# QCopterRC_MCU_Sch.net
KiCad netlist of a schematic drawn in Altium Designer
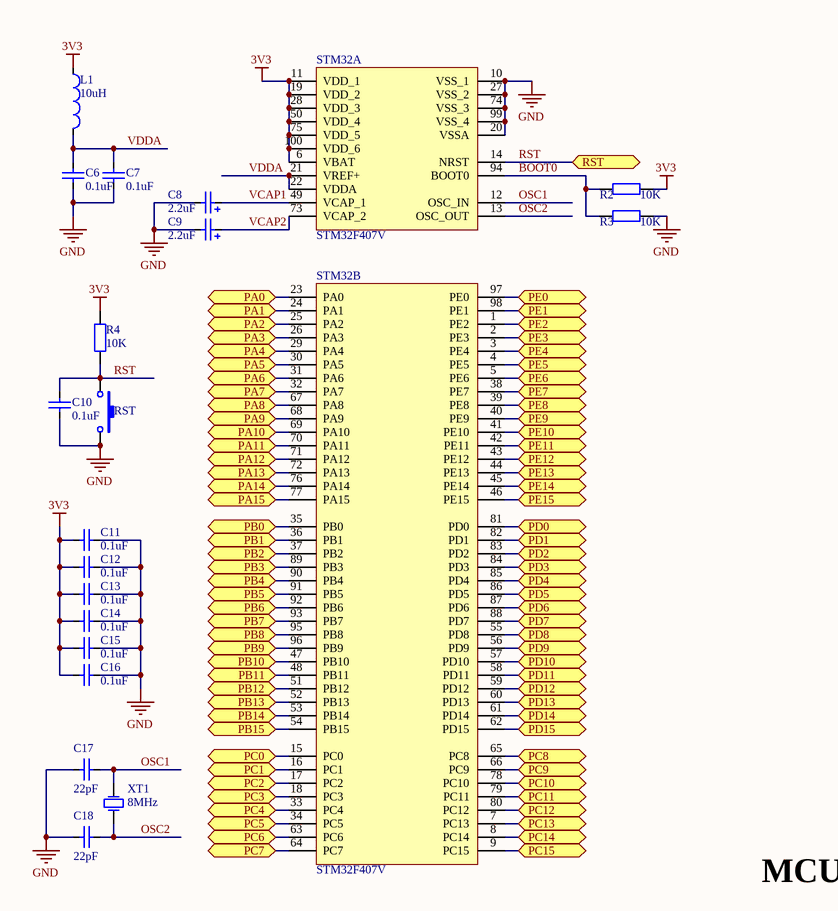
[diagram p0: QCopterRC_MCU_Sch.SchDoc]

(export (version "E")
  (design (tool "Eeschema 10.0.6"))
  (components
    (comp (ref "C6")
      (value "0.1uF")
      (footprint "PCB_Passive:CAP_0603")
      (description "Capacitor")
      (fields (field (name "Comment") "Cap_0603"))
      (libsource (lib "SCH_Passive") (part "Cap_0603"))
    )
    (comp (ref "C7")
      (value "0.1uF")
      (footprint "PCB_Passive:CAP_0603")
      (description "Capacitor")
      (fields (field (name "Comment") "Cap_0603"))
      (libsource (lib "SCH_Passive") (part "Cap_0603"))
    )
    (comp (ref "C8")
      (value "2.2uF")
      (footprint "PCB_Passive:CAP_TAN_P0805")
      (description "Capacitor")
      (fields (field (name "Comment") "Cap_Tan_0805"))
      (libsource (lib "SCH_Passive") (part "Cap_Tan_0805"))
    )
    (comp (ref "C9")
      (value "2.2uF")
      (footprint "PCB_Passive:CAP_TAN_P0805")
      (description "Capacitor")
      (fields (field (name "Comment") "Cap_Tan_0805"))
      (libsource (lib "SCH_Passive") (part "Cap_Tan_0805"))
    )
    (comp (ref "C10")
      (value "0.1uF")
      (footprint "PCB_Passive:CAP_0603")
      (description "Capacitor")
      (fields (field (name "Comment") "Cap_0603"))
      (libsource (lib "SCH_Passive") (part "Cap_0603"))
    )
    (comp (ref "C11")
      (value "0.1uF")
      (footprint "PCB_Passive:CAP_0603")
      (description "Capacitor")
      (fields (field (name "Comment") "Cap_0603"))
      (libsource (lib "SCH_Passive") (part "Cap_0603"))
    )
    (comp (ref "C12")
      (value "0.1uF")
      (footprint "PCB_Passive:CAP_0603")
      (description "Capacitor")
      (fields (field (name "Comment") "Cap_0603"))
      (libsource (lib "SCH_Passive") (part "Cap_0603"))
    )
    (comp (ref "C13")
      (value "0.1uF")
      (footprint "PCB_Passive:CAP_0603")
      (description "Capacitor")
      (fields (field (name "Comment") "Cap_0603"))
      (libsource (lib "SCH_Passive") (part "Cap_0603"))
    )
    (comp (ref "C14")
      (value "0.1uF")
      (footprint "PCB_Passive:CAP_0603")
      (description "Capacitor")
      (fields (field (name "Comment") "Cap_0603"))
      (libsource (lib "SCH_Passive") (part "Cap_0603"))
    )
    (comp (ref "C15")
      (value "0.1uF")
      (footprint "PCB_Passive:CAP_0603")
      (description "Capacitor")
      (fields (field (name "Comment") "Cap_0603"))
      (libsource (lib "SCH_Passive") (part "Cap_0603"))
    )
    (comp (ref "C16")
      (value "0.1uF")
      (footprint "PCB_Passive:CAP_0603")
      (description "Capacitor")
      (fields (field (name "Comment") "Cap_0603"))
      (libsource (lib "SCH_Passive") (part "Cap_0603"))
    )
    (comp (ref "C17")
      (value "22pF")
      (footprint "PCB_Passive:CAP_0603")
      (description "Capacitor")
      (fields (field (name "Comment") "Cap_0603"))
      (libsource (lib "SCH_Passive") (part "Cap_0603"))
    )
    (comp (ref "C18")
      (value "22pF")
      (footprint "PCB_Passive:CAP_0603")
      (description "Capacitor")
      (fields (field (name "Comment") "Cap_0603"))
      (libsource (lib "SCH_Passive") (part "Cap_0603"))
    )
    (comp (ref "L1")
      (value "10uH")
      (footprint "PCB_Passive:IND_0603")
      (description "Inductor")
      (fields (field (name "Comment") "Ind_0603"))
      (libsource (lib "SCH_Passive") (part "Ind_0603"))
    )
    (comp (ref "R2")
      (value "10K")
      (footprint "PCB_Passive:RES_0603")
      (description "Resistor")
      (fields (field (name "Comment") "Res_0603"))
      (libsource (lib "SCH_Passive") (part "Res_0603"))
    )
    (comp (ref "R3")
      (value "10K")
      (footprint "PCB_Passive:RES_0603")
      (description "Resistor")
      (fields (field (name "Comment") "Res_0603"))
      (libsource (lib "SCH_Passive") (part "Res_0603"))
    )
    (comp (ref "R4")
      (value "10K")
      (footprint "PCB_Passive:RES_0603")
      (description "Resistor")
      (fields (field (name "Comment") "Res_0603"))
      (libsource (lib "") (part "Res_0603_1"))
    )
    (comp (ref "RST")
      (value "BT_TACT_3x6_180")
      (footprint "PCB_Switch:BT_TACT_3x6_180")
      (description "Switch")
      (libsource (lib "SCH_Switch") (part "BT_TACT_3x6_180"))
    )
    (comp (ref "STM32")
      (value "STM32F407V")
      (footprint "PCB_IC:STM32F_100")
      (description "MCU")
      (libsource (lib "SCH_IC") (part "STM32F407V"))
    )
    (comp (ref "XT1")
      (value "8MHz")
      (footprint "PCB_Oscillator:XTAL_5032")
      (description "Crystal Oscillator")
      (fields (field (name "Comment") "XTAL_5032") (field (name "PUBLISHER") "Altium Limited"))
      (libsource (lib "SCH_Oscillator") (part "XTAL_5032"))
    )
  )
  (nets
    (net (code "1") (name "/BOOT0") (class "Default")
      (node (ref "R2") (pin "1") (pinfunction "1_1") (pintype "passive"))
      (node (ref "R3") (pin "1") (pinfunction "1_1") (pintype "passive"))
      (node (ref "STM32") (pin "94") (pinfunction "BOOT0_94") (pintype "passive"))
    )
    (net (code "2") (name "/OSC1") (class "Default")
      (node (ref "C17") (pin "2") (pinfunction "2_2") (pintype "passive"))
      (node (ref "STM32") (pin "12") (pinfunction "OSC_IN_12") (pintype "passive"))
      (node (ref "XT1") (pin "2") (pinfunction "OSC2_2") (pintype "passive"))
    )
    (net (code "3") (name "/OSC2") (class "Default")
      (node (ref "C18") (pin "2") (pinfunction "2_2") (pintype "passive"))
      (node (ref "STM32") (pin "13") (pinfunction "OSC_OUT_13") (pintype "passive"))
      (node (ref "XT1") (pin "1") (pinfunction "OSC1_1") (pintype "passive"))
    )
    (net (code "4") (name "/PA0") (class "Default")
      (node (ref "STM32") (pin "23") (pinfunction "PA0_23") (pintype "passive"))
    )
    (net (code "5") (name "/PA1") (class "Default")
      (node (ref "STM32") (pin "24") (pinfunction "PA1_24") (pintype "passive"))
    )
    (net (code "6") (name "/PA2") (class "Default")
      (node (ref "STM32") (pin "25") (pinfunction "PA2_25") (pintype "passive"))
    )
    (net (code "7") (name "/PA3") (class "Default")
      (node (ref "STM32") (pin "26") (pinfunction "PA3_26") (pintype "passive"))
    )
    (net (code "8") (name "/PA4") (class "Default")
      (node (ref "STM32") (pin "29") (pinfunction "PA4_29") (pintype "passive"))
    )
    (net (code "9") (name "/PA5") (class "Default")
      (node (ref "STM32") (pin "30") (pinfunction "PA5_30") (pintype "passive"))
    )
    (net (code "10") (name "/PA6") (class "Default")
      (node (ref "STM32") (pin "31") (pinfunction "PA6_31") (pintype "passive"))
    )
    (net (code "11") (name "/PA7") (class "Default")
      (node (ref "STM32") (pin "32") (pinfunction "PA7_32") (pintype "passive"))
    )
    (net (code "12") (name "/PA8") (class "Default")
      (node (ref "STM32") (pin "67") (pinfunction "PA8_67") (pintype "passive"))
    )
    (net (code "13") (name "/PA9") (class "Default")
      (node (ref "STM32") (pin "68") (pinfunction "PA9_68") (pintype "passive"))
    )
    (net (code "14") (name "/PA10") (class "Default")
      (node (ref "STM32") (pin "69") (pinfunction "PA10_69") (pintype "passive"))
    )
    (net (code "15") (name "/PA11") (class "Default")
      (node (ref "STM32") (pin "70") (pinfunction "PA11_70") (pintype "passive"))
    )
    (net (code "16") (name "/PA12") (class "Default")
      (node (ref "STM32") (pin "71") (pinfunction "PA12_71") (pintype "passive"))
    )
    (net (code "17") (name "/PA13") (class "Default")
      (node (ref "STM32") (pin "72") (pinfunction "PA13_72") (pintype "passive"))
    )
    (net (code "18") (name "/PA14") (class "Default")
      (node (ref "STM32") (pin "76") (pinfunction "PA14_76") (pintype "passive"))
    )
    (net (code "19") (name "/PA15") (class "Default")
      (node (ref "STM32") (pin "77") (pinfunction "PA15_77") (pintype "passive"))
    )
    (net (code "20") (name "/PB0") (class "Default")
      (node (ref "STM32") (pin "35") (pinfunction "PB0_35") (pintype "passive"))
    )
    (net (code "21") (name "/PB1") (class "Default")
      (node (ref "STM32") (pin "36") (pinfunction "PB1_36") (pintype "passive"))
    )
    (net (code "22") (name "/PB2") (class "Default")
      (node (ref "STM32") (pin "37") (pinfunction "PB2_37") (pintype "passive"))
    )
    (net (code "23") (name "/PB3") (class "Default")
      (node (ref "STM32") (pin "89") (pinfunction "PB3_89") (pintype "passive"))
    )
    (net (code "24") (name "/PB4") (class "Default")
      (node (ref "STM32") (pin "90") (pinfunction "PB4_90") (pintype "passive"))
    )
    (net (code "25") (name "/PB5") (class "Default")
      (node (ref "STM32") (pin "91") (pinfunction "PB5_91") (pintype "passive"))
    )
    (net (code "26") (name "/PB6") (class "Default")
      (node (ref "STM32") (pin "92") (pinfunction "PB6_92") (pintype "passive"))
    )
    (net (code "27") (name "/PB7") (class "Default")
      (node (ref "STM32") (pin "93") (pinfunction "PB7_93") (pintype "passive"))
    )
    (net (code "28") (name "/PB8") (class "Default")
      (node (ref "STM32") (pin "95") (pinfunction "PB8_95") (pintype "passive"))
    )
    (net (code "29") (name "/PB9") (class "Default")
      (node (ref "STM32") (pin "96") (pinfunction "PB9_96") (pintype "passive"))
    )
    (net (code "30") (name "/PB10") (class "Default")
      (node (ref "STM32") (pin "47") (pinfunction "PB10_47") (pintype "passive"))
    )
    (net (code "31") (name "/PB11") (class "Default")
      (node (ref "STM32") (pin "48") (pinfunction "PB11_48") (pintype "passive"))
    )
    (net (code "32") (name "/PB12") (class "Default")
      (node (ref "STM32") (pin "51") (pinfunction "PB12_51") (pintype "passive"))
    )
    (net (code "33") (name "/PB13") (class "Default")
      (node (ref "STM32") (pin "52") (pinfunction "PB13_52") (pintype "passive"))
    )
    (net (code "34") (name "/PB14") (class "Default")
      (node (ref "STM32") (pin "53") (pinfunction "PB14_53") (pintype "passive"))
    )
    (net (code "35") (name "/PB15") (class "Default")
      (node (ref "STM32") (pin "54") (pinfunction "PB15_54") (pintype "passive"))
    )
    (net (code "36") (name "/PC0") (class "Default")
      (node (ref "STM32") (pin "15") (pinfunction "PC0_15") (pintype "passive"))
    )
    (net (code "37") (name "/PC1") (class "Default")
      (node (ref "STM32") (pin "16") (pinfunction "PC1_16") (pintype "passive"))
    )
    (net (code "38") (name "/PC2") (class "Default")
      (node (ref "STM32") (pin "17") (pinfunction "PC2_17") (pintype "passive"))
    )
    (net (code "39") (name "/PC3") (class "Default")
      (node (ref "STM32") (pin "18") (pinfunction "PC3_18") (pintype "passive"))
    )
    (net (code "40") (name "/PC4") (class "Default")
      (node (ref "STM32") (pin "33") (pinfunction "PC4_33") (pintype "passive"))
    )
    (net (code "41") (name "/PC5") (class "Default")
      (node (ref "STM32") (pin "34") (pinfunction "PC5_34") (pintype "passive"))
    )
    (net (code "42") (name "/PC6") (class "Default")
      (node (ref "STM32") (pin "63") (pinfunction "PC6_63") (pintype "passive"))
    )
    (net (code "43") (name "/PC7") (class "Default")
      (node (ref "STM32") (pin "64") (pinfunction "PC7_64") (pintype "passive"))
    )
    (net (code "44") (name "/PC8") (class "Default")
      (node (ref "STM32") (pin "65") (pinfunction "PC8_65") (pintype "passive"))
    )
    (net (code "45") (name "/PC9") (class "Default")
      (node (ref "STM32") (pin "66") (pinfunction "PC9_66") (pintype "passive"))
    )
    (net (code "46") (name "/PC10") (class "Default")
      (node (ref "STM32") (pin "78") (pinfunction "PC10_78") (pintype "passive"))
    )
    (net (code "47") (name "/PC11") (class "Default")
      (node (ref "STM32") (pin "79") (pinfunction "PC11_79") (pintype "passive"))
    )
    (net (code "48") (name "/PC12") (class "Default")
      (node (ref "STM32") (pin "80") (pinfunction "PC12_80") (pintype "passive"))
    )
    (net (code "49") (name "/PC13") (class "Default")
      (node (ref "STM32") (pin "7") (pinfunction "PC13_7") (pintype "passive"))
    )
    (net (code "50") (name "/PC14") (class "Default")
      (node (ref "STM32") (pin "8") (pinfunction "PC14_8") (pintype "passive"))
    )
    (net (code "51") (name "/PC15") (class "Default")
      (node (ref "STM32") (pin "9") (pinfunction "PC15_9") (pintype "passive"))
    )
    (net (code "52") (name "/PD0") (class "Default")
      (node (ref "STM32") (pin "81") (pinfunction "PD0_81") (pintype "passive"))
    )
    (net (code "53") (name "/PD1") (class "Default")
      (node (ref "STM32") (pin "82") (pinfunction "PD1_82") (pintype "passive"))
    )
    (net (code "54") (name "/PD2") (class "Default")
      (node (ref "STM32") (pin "83") (pinfunction "PD2_83") (pintype "passive"))
    )
    (net (code "55") (name "/PD3") (class "Default")
      (node (ref "STM32") (pin "84") (pinfunction "PD3_84") (pintype "passive"))
    )
    (net (code "56") (name "/PD4") (class "Default")
      (node (ref "STM32") (pin "85") (pinfunction "PD4_85") (pintype "passive"))
    )
    (net (code "57") (name "/PD5") (class "Default")
      (node (ref "STM32") (pin "86") (pinfunction "PD5_86") (pintype "passive"))
    )
    (net (code "58") (name "/PD6") (class "Default")
      (node (ref "STM32") (pin "87") (pinfunction "PD6_87") (pintype "passive"))
    )
    (net (code "59") (name "/PD7") (class "Default")
      (node (ref "STM32") (pin "88") (pinfunction "PD7_88") (pintype "passive"))
    )
    (net (code "60") (name "/PD8") (class "Default")
      (node (ref "STM32") (pin "55") (pinfunction "PD8_55") (pintype "passive"))
    )
    (net (code "61") (name "/PD9") (class "Default")
      (node (ref "STM32") (pin "56") (pinfunction "PD9_56") (pintype "passive"))
    )
    (net (code "62") (name "/PD10") (class "Default")
      (node (ref "STM32") (pin "57") (pinfunction "PD10_57") (pintype "passive"))
    )
    (net (code "63") (name "/PD11") (class "Default")
      (node (ref "STM32") (pin "58") (pinfunction "PD11_58") (pintype "passive"))
    )
    (net (code "64") (name "/PD12") (class "Default")
      (node (ref "STM32") (pin "59") (pinfunction "PD12_59") (pintype "passive"))
    )
    (net (code "65") (name "/PD13") (class "Default")
      (node (ref "STM32") (pin "60") (pinfunction "PD13_60") (pintype "passive"))
    )
    (net (code "66") (name "/PD14") (class "Default")
      (node (ref "STM32") (pin "61") (pinfunction "PD14_61") (pintype "passive"))
    )
    (net (code "67") (name "/PD15") (class "Default")
      (node (ref "STM32") (pin "62") (pinfunction "PD15_62") (pintype "passive"))
    )
    (net (code "68") (name "/PE0") (class "Default")
      (node (ref "STM32") (pin "97") (pinfunction "PE0_97") (pintype "passive"))
    )
    (net (code "69") (name "/PE1") (class "Default")
      (node (ref "STM32") (pin "98") (pinfunction "PE1_98") (pintype "passive"))
    )
    (net (code "70") (name "/PE2") (class "Default")
      (node (ref "STM32") (pin "1") (pinfunction "PE2_1") (pintype "passive"))
    )
    (net (code "71") (name "/PE3") (class "Default")
      (node (ref "STM32") (pin "2") (pinfunction "PE3_2") (pintype "passive"))
    )
    (net (code "72") (name "/PE4") (class "Default")
      (node (ref "STM32") (pin "3") (pinfunction "PE4_3") (pintype "passive"))
    )
    (net (code "73") (name "/PE5") (class "Default")
      (node (ref "STM32") (pin "4") (pinfunction "PE5_4") (pintype "passive"))
    )
    (net (code "74") (name "/PE6") (class "Default")
      (node (ref "STM32") (pin "5") (pinfunction "PE6_5") (pintype "passive"))
    )
    (net (code "75") (name "/PE7") (class "Default")
      (node (ref "STM32") (pin "38") (pinfunction "PE7_38") (pintype "passive"))
    )
    (net (code "76") (name "/PE8") (class "Default")
      (node (ref "STM32") (pin "39") (pinfunction "PE8_39") (pintype "passive"))
    )
    (net (code "77") (name "/PE9") (class "Default")
      (node (ref "STM32") (pin "40") (pinfunction "PE9_40") (pintype "passive"))
    )
    (net (code "78") (name "/PE10") (class "Default")
      (node (ref "STM32") (pin "41") (pinfunction "PE10_41") (pintype "passive"))
    )
    (net (code "79") (name "/PE11") (class "Default")
      (node (ref "STM32") (pin "42") (pinfunction "PE11_42") (pintype "passive"))
    )
    (net (code "80") (name "/PE12") (class "Default")
      (node (ref "STM32") (pin "43") (pinfunction "PE12_43") (pintype "passive"))
    )
    (net (code "81") (name "/PE13") (class "Default")
      (node (ref "STM32") (pin "44") (pinfunction "PE13_44") (pintype "passive"))
    )
    (net (code "82") (name "/PE14") (class "Default")
      (node (ref "STM32") (pin "45") (pinfunction "PE14_45") (pintype "passive"))
    )
    (net (code "83") (name "/PE15") (class "Default")
      (node (ref "STM32") (pin "46") (pinfunction "PE15_46") (pintype "passive"))
    )
    (net (code "84") (name "/RST") (class "Default")
      (node (ref "C10") (pin "1") (pinfunction "1_1") (pintype "passive"))
      (node (ref "R4") (pin "2") (pinfunction "2_2") (pintype "passive"))
      (node (ref "RST") (pin "1") (pinfunction "1_1") (pintype "passive"))
      (node (ref "STM32") (pin "14") (pinfunction "NRST_14") (pintype "passive"))
    )
    (net (code "85") (name "/VCAP1") (class "Default")
      (node (ref "C8") (pin "1") (pinfunction "1_1") (pintype "passive"))
      (node (ref "STM32") (pin "49") (pinfunction "VCAP_1_49") (pintype "passive"))
    )
    (net (code "86") (name "/VCAP2") (class "Default")
      (node (ref "C9") (pin "1") (pinfunction "1_1") (pintype "passive"))
      (node (ref "STM32") (pin "73") (pinfunction "VCAP_2_73") (pintype "passive"))
    )
    (net (code "87") (name "/VDDA") (class "Default")
      (node (ref "C6") (pin "1") (pinfunction "1_1") (pintype "passive"))
      (node (ref "C7") (pin "1") (pinfunction "1_1") (pintype "passive"))
      (node (ref "L1") (pin "2") (pinfunction "2_2") (pintype "passive"))
      (node (ref "STM32") (pin "21") (pinfunction "VREF+_21") (pintype "passive"))
      (node (ref "STM32") (pin "22") (pinfunction "VDDA_22") (pintype "passive"))
    )
    (net (code "88") (name "3V3") (class "Default")
      (node (ref "C11") (pin "2") (pinfunction "2_2") (pintype "passive"))
      (node (ref "C12") (pin "2") (pinfunction "2_2") (pintype "passive"))
      (node (ref "C13") (pin "2") (pinfunction "2_2") (pintype "passive"))
      (node (ref "C14") (pin "2") (pinfunction "2_2") (pintype "passive"))
      (node (ref "C15") (pin "2") (pinfunction "2_2") (pintype "passive"))
      (node (ref "C16") (pin "2") (pinfunction "2_2") (pintype "passive"))
      (node (ref "L1") (pin "1") (pinfunction "1_1") (pintype "passive"))
      (node (ref "R2") (pin "2") (pinfunction "2_2") (pintype "passive"))
      (node (ref "R4") (pin "1") (pinfunction "1_1") (pintype "passive"))
      (node (ref "STM32") (pin "100") (pinfunction "VDD_6_100") (pintype "passive"))
      (node (ref "STM32") (pin "11") (pinfunction "VDD_1_11") (pintype "passive"))
      (node (ref "STM32") (pin "19") (pinfunction "VDD_2_19") (pintype "passive"))
      (node (ref "STM32") (pin "28") (pinfunction "VDD_3_28") (pintype "passive"))
      (node (ref "STM32") (pin "50") (pinfunction "VDD_4_50") (pintype "passive"))
      (node (ref "STM32") (pin "6") (pinfunction "VBAT_6") (pintype "passive"))
      (node (ref "STM32") (pin "75") (pinfunction "VDD_5_75") (pintype "passive"))
    )
    (net (code "89") (name "GND") (class "Default")
      (node (ref "C10") (pin "2") (pinfunction "2_2") (pintype "passive"))
      (node (ref "C11") (pin "1") (pinfunction "1_1") (pintype "passive"))
      (node (ref "C12") (pin "1") (pinfunction "1_1") (pintype "passive"))
      (node (ref "C13") (pin "1") (pinfunction "1_1") (pintype "passive"))
      (node (ref "C14") (pin "1") (pinfunction "1_1") (pintype "passive"))
      (node (ref "C15") (pin "1") (pinfunction "1_1") (pintype "passive"))
      (node (ref "C16") (pin "1") (pinfunction "1_1") (pintype "passive"))
      (node (ref "C17") (pin "1") (pinfunction "1_1") (pintype "passive"))
      (node (ref "C18") (pin "1") (pinfunction "1_1") (pintype "passive"))
      (node (ref "C6") (pin "2") (pinfunction "2_2") (pintype "passive"))
      (node (ref "C7") (pin "2") (pinfunction "2_2") (pintype "passive"))
      (node (ref "C8") (pin "2") (pinfunction "2_2") (pintype "passive"))
      (node (ref "C9") (pin "2") (pinfunction "2_2") (pintype "passive"))
      (node (ref "R3") (pin "2") (pinfunction "2_2") (pintype "passive"))
      (node (ref "RST") (pin "2") (pinfunction "2_2") (pintype "passive"))
      (node (ref "STM32") (pin "10") (pinfunction "VSS_1_10") (pintype "passive"))
      (node (ref "STM32") (pin "20") (pinfunction "VSSA_20") (pintype "passive"))
      (node (ref "STM32") (pin "27") (pinfunction "VSS_2_27") (pintype "passive"))
      (node (ref "STM32") (pin "74") (pinfunction "VSS_3_74") (pintype "passive"))
      (node (ref "STM32") (pin "99") (pinfunction "VSS_4_99") (pintype "passive"))
    )
  )
)
